# 9_-_UV_OV_Protection.net
KiCad netlist of a schematic drawn in Altium Designer
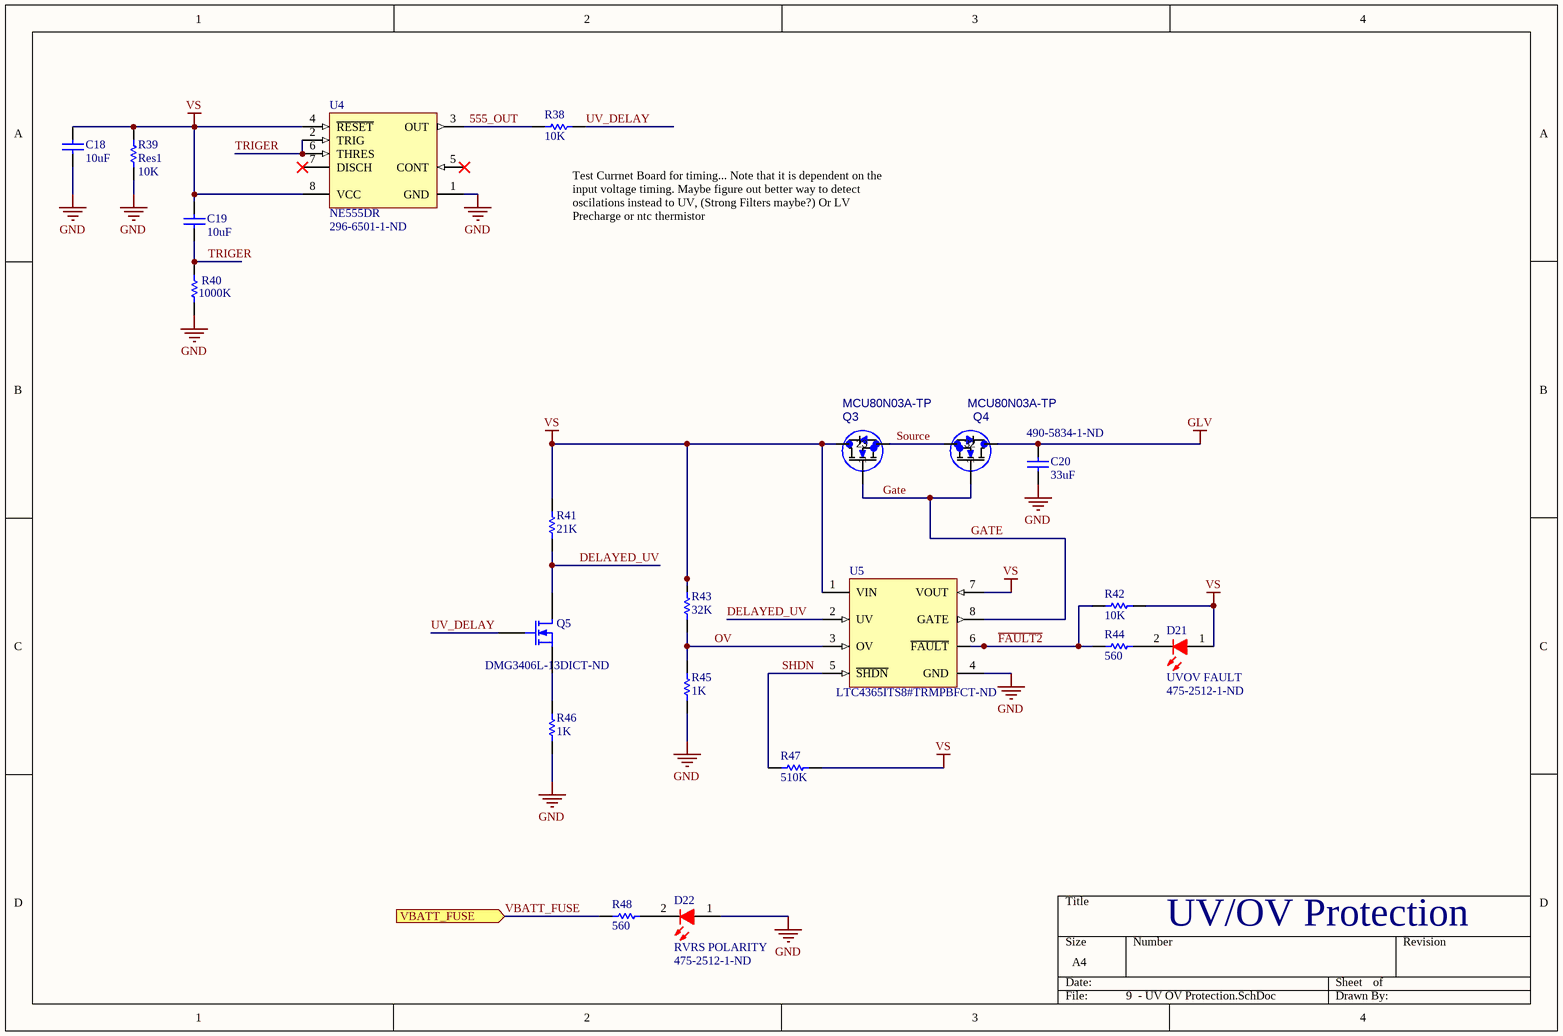
[diagram p0: 9  - UV OV Protection.SchDoc]

(export (version "E")
  (design (tool "Eeschema 10.0.6"))
  (components
    (comp (ref "C18")
      (value "10uF")
      (footprint "1608[0603]")
      (description "Capacitor (Semiconductor SIM Model)")
      (fields (field (name "Comment") "Cap Semi") (field (name "PUBLISHER") "Altium Limited"))
      (libsource (lib "Miscellaneous Devices") (part "Cap Semi"))
    )
    (comp (ref "C19")
      (value "10uF")
      (footprint "1608[0603]")
      (description "Capacitor (Semiconductor SIM Model)")
      (fields (field (name "Comment") "Cap Semi") (field (name "PUBLISHER") "Altium Limited"))
      (libsource (lib "Miscellaneous Devices") (part "Cap Semi"))
    )
    (comp (ref "C20")
      (value "33uF")
      (footprint "2J-Lead 6.1 x 5.3")
      (description "Capacitor (Semiconductor SIM Model)")
      (fields
        (field (name "SUPPLIER PART NUMBER 1") "490-5834-1-ND")
        (field (name "Comment") "Cap Semi")
        (field (name "PUBLISHER") "Altium Limited")
      )
      (libsource (lib "Miscellaneous Devices") (part "Cap Semi"))
    )
    (comp (ref "D21")
      (value "UVOV FAULT")
      (footprint "TOSH-0603LED_RED_V")
      (description "LED, Red 0603 (1608) 63mCd")
      (fields
        (field (name "MANUFACTURER") "Toshiba")
        (field (name "PARTNUMBER") "TLSU1008A(T04)")
        (field (name "SUPPLIER PART NUMBER 1") "475-2512-1-ND")
      )
      (libsource (lib "Altium Content Vault") (part "CMP-0444-00001-1"))
    )
    (comp (ref "D22")
      (value "RVRS POLARITY")
      (footprint "TOSH-0603LED_RED_V")
      (description "LED, Red 0603 (1608) 63mCd")
      (fields
        (field (name "MANUFACTURER") "Toshiba")
        (field (name "PARTNUMBER") "TLSU1008A(T04)")
        (field (name "SUPPLIER PART NUMBER 1") "475-2512-1-ND")
      )
      (libsource (lib "Altium Content Vault") (part "CMP-0444-00001-1"))
    )
    (comp (ref "Q3")
      (value "MCU80N03A-TP")
      (footprint "MCU80N_MCE")
      (fields (field (name "COPYRIGHT") "Copyright (C) 2022 Ultra Librarian. All rights reserved."))
      (libsource (lib "ACB_lib") (part "MCU80N03A-TP"))
    )
    (comp (ref "Q4")
      (value "MCU80N03A-TP")
      (footprint "MCU80N_MCE")
      (fields (field (name "COPYRIGHT") "Copyright (C) 2022 Ultra Librarian. All rights reserved."))
      (libsource (lib "ACB_lib") (part "MCU80N03A-TP"))
    )
    (comp (ref "Q5")
      (value "~")
      (footprint "SOT-23_N")
      (description "N-Channel MOSFET")
      (fields
        (field (name "MANUFACTURER") "Infineon Technologies")
        (field (name "MANUFACTURER PART NUMBER") "IPD075N03L G")
        (field (name "SUPPLIER PART NUMBER 1") "DMG3406L-13DICT-ND")
        (field (name "PUBLISHER") "Altium Limited")
      )
      (libsource (lib "Miscellaneous Devices") (part "MOSFET-N"))
    )
    (comp (ref "R38")
      (value "10K")
      (footprint "RESC0603(1608)_L")
      (description "0603 (1608 Metric) Chip Resistor")
      (libsource (lib "Altium Content Vault") (part "RES_3"))
    )
    (comp (ref "R39")
      (value "Res1")
      (footprint "1608[0603]")
      (description "RES SMD 10K OHM 5% 1/4W 0603")
      (fields
        (field (name "ALTIUM_VALUE") "10K")
        (field (name "MANUFACTURER") "Rohm Semiconductor")
        (field (name "MANUFACTURER PART NUMBER") "ESR03EZPJ103")
        (field (name "PUBLISHER") "Altium Limited")
      )
      (libsource (lib "Miscellaneous Devices") (part "Res1"))
    )
    (comp (ref "R40")
      (value "1000K")
      (footprint "RESC0603(1608)_L")
      (description "0603 (1608 Metric) Chip Resistor")
      (libsource (lib "Altium Content Vault") (part "RES_3"))
    )
    (comp (ref "R41")
      (value "21K")
      (footprint "RESC0603(1608)_L")
      (description "0603 (1608 Metric) Chip Resistor")
      (libsource (lib "Altium Content Vault") (part "RES_3"))
    )
    (comp (ref "R42")
      (value "10K")
      (footprint "RESC0603(1608)_L")
      (description "0603 (1608 Metric) Chip Resistor")
      (libsource (lib "Altium Content Vault") (part "RES_3"))
    )
    (comp (ref "R43")
      (value "32K")
      (footprint "RESC0603(1608)_L")
      (description "0603 (1608 Metric) Chip Resistor")
      (libsource (lib "Altium Content Vault") (part "RES_3"))
    )
    (comp (ref "R44")
      (value "560")
      (footprint "RESC0603(1608)_L")
      (description "0603 (1608 Metric) Chip Resistor")
      (libsource (lib "Altium Content Vault") (part "RES_3"))
    )
    (comp (ref "R45")
      (value "1K")
      (footprint "RESC0603(1608)_L")
      (description "0603 (1608 Metric) Chip Resistor")
      (libsource (lib "Altium Content Vault") (part "RES_3"))
    )
    (comp (ref "R46")
      (value "1K")
      (footprint "RESC0603(1608)_L")
      (description "0603 (1608 Metric) Chip Resistor")
      (libsource (lib "Altium Content Vault") (part "RES_3"))
    )
    (comp (ref "R47")
      (value "510K")
      (footprint "RESC0603(1608)_L")
      (description "0603 (1608 Metric) Chip Resistor")
      (libsource (lib "Altium Content Vault") (part "RES_3"))
    )
    (comp (ref "R48")
      (value "560")
      (footprint "RESC0603(1608)_L")
      (description "0603 (1608 Metric) Chip Resistor")
      (libsource (lib "Altium Content Vault") (part "RES_3"))
    )
    (comp (ref "U4")
      (value "NE555DR")
      (footprint "D0008A_M")
      (fields (field (name "SUPPLIER PART NUMBER 1") "296-6501-1-ND"))
      (libsource (lib "Altium Content Vault") (part "CMP-1685-00007-1"))
    )
    (comp (ref "U5")
      (value "LTC4365ITS8#TRMPBF")
      (footprint "LT-TS8-8-TSOT-23_V")
      (fields
        (field (name "MANUFACTURER") "Linear Technology")
        (field (name "SUPPLIER PART NUMBER 1") "LTC4365ITS8#TRMPBFCT-ND")
      )
      (libsource (lib "Altium Content Vault") (part "LT-LTC4365-TS8-8"))
    )
  )
  (nets
    (net (code "1") (name "/555_OUT") (class "Default")
      (node (ref "R38") (pin "1") (pinfunction "1_1") (pintype "passive"))
      (node (ref "U4") (pin "3") (pinfunction "OUT_3") (pintype "output"))
    )
    (net (code "2") (name "/DELAYED_UV") (class "Default")
      (node (ref "Q5") (pin "3") (pinfunction "D_3") (pintype "passive"))
      (node (ref "R41") (pin "2") (pinfunction "2_2") (pintype "passive"))
      (node (ref "U5") (pin "2") (pinfunction "UV_2") (pintype "input"))
    )
    (net (code "3") (name "/GATE") (class "Default")
      (node (ref "Q3") (pin "1") (pinfunction "1_1") (pintype "passive"))
      (node (ref "Q4") (pin "1") (pinfunction "1_1") (pintype "passive"))
      (node (ref "U5") (pin "8") (pinfunction "GATE_8") (pintype "output"))
    )
    (net (code "4") (name "/OV") (class "Default")
      (node (ref "R43") (pin "1") (pinfunction "1_1") (pintype "passive"))
      (node (ref "R45") (pin "2") (pinfunction "2_2") (pintype "passive"))
      (node (ref "U5") (pin "3") (pinfunction "OV_3") (pintype "input"))
    )
    (net (code "5") (name "/SHDN") (class "Default")
      (node (ref "R47") (pin "2") (pinfunction "2_2") (pintype "passive"))
      (node (ref "U5") (pin "5") (pinfunction "~{SHDN}_5") (pintype "input"))
    )
    (net (code "6") (name "/Source") (class "Default")
      (node (ref "Q3") (pin "3") (pinfunction "3_3") (pintype "passive"))
      (node (ref "Q4") (pin "3") (pinfunction "3_3") (pintype "passive"))
    )
    (net (code "7") (name "/TRIGER") (class "Default")
      (node (ref "C19") (pin "1") (pinfunction "1_1") (pintype "passive"))
      (node (ref "R40") (pin "2") (pinfunction "2_2") (pintype "passive"))
      (node (ref "U4") (pin "2") (pinfunction "TRIG_2") (pintype "input"))
      (node (ref "U4") (pin "6") (pinfunction "THRES_6") (pintype "input"))
    )
    (net (code "8") (name "/UV_DELAY") (class "Default")
      (node (ref "Q5") (pin "1") (pinfunction "G_1") (pintype "passive"))
      (node (ref "R38") (pin "2") (pinfunction "2_2") (pintype "passive"))
    )
    (net (code "9") (name "/VBATT_FUSE") (class "Default")
      (node (ref "R48") (pin "1") (pinfunction "1_1") (pintype "passive"))
    )
    (net (code "10") (name "/~{FAULT2}") (class "Default")
      (node (ref "R42") (pin "2") (pinfunction "2_2") (pintype "passive"))
      (node (ref "R44") (pin "1") (pinfunction "1_1") (pintype "passive"))
      (node (ref "U5") (pin "6") (pinfunction "~{FAULT}_6") (pintype "open_collector"))
    )
    (net (code "11") (name "GLV") (class "Default")
      (node (ref "C20") (pin "1") (pinfunction "1_1") (pintype "passive"))
      (node (ref "Q4") (pin "2") (pinfunction "2_2") (pintype "passive"))
    )
    (net (code "12") (name "GND") (class "Default")
      (node (ref "C18") (pin "1") (pinfunction "1_1") (pintype "passive"))
      (node (ref "C20") (pin "2") (pinfunction "2_2") (pintype "passive"))
      (node (ref "D22") (pin "1") (pinfunction "A_1") (pintype "passive"))
      (node (ref "R39") (pin "1") (pinfunction "1_1") (pintype "passive"))
      (node (ref "R40") (pin "1") (pinfunction "1_1") (pintype "passive"))
      (node (ref "R45") (pin "1") (pinfunction "1_1") (pintype "passive"))
      (node (ref "R46") (pin "2") (pinfunction "2_2") (pintype "passive"))
      (node (ref "U4") (pin "1") (pinfunction "GND_1") (pintype "power_in"))
      (node (ref "U5") (pin "4") (pinfunction "GND_4") (pintype "power_in"))
    )
    (net (code "13") (name "Net-(D21-K)") (class "Default")
      (node (ref "D21") (pin "2") (pinfunction "K_2") (pintype "passive"))
      (node (ref "R44") (pin "2") (pinfunction "2_2") (pintype "passive"))
    )
    (net (code "14") (name "Net-(D22-K)") (class "Default")
      (node (ref "D22") (pin "2") (pinfunction "K_2") (pintype "passive"))
      (node (ref "R48") (pin "2") (pinfunction "2_2") (pintype "passive"))
    )
    (net (code "15") (name "Net-(Q5-S)") (class "Default")
      (node (ref "Q5") (pin "2") (pinfunction "S_2") (pintype "passive"))
      (node (ref "R46") (pin "1") (pinfunction "1_1") (pintype "passive"))
    )
    (net (code "16") (name "VS") (class "Default")
      (node (ref "C18") (pin "2") (pinfunction "2_2") (pintype "passive"))
      (node (ref "C19") (pin "2") (pinfunction "2_2") (pintype "passive"))
      (node (ref "D21") (pin "1") (pinfunction "A_1") (pintype "passive"))
      (node (ref "Q3") (pin "2") (pinfunction "2_2") (pintype "passive"))
      (node (ref "R39") (pin "2") (pinfunction "2_2") (pintype "passive"))
      (node (ref "R41") (pin "1") (pinfunction "1_1") (pintype "passive"))
      (node (ref "R42") (pin "1") (pinfunction "1_1") (pintype "passive"))
      (node (ref "R43") (pin "2") (pinfunction "2_2") (pintype "passive"))
      (node (ref "R47") (pin "1") (pinfunction "1_1") (pintype "passive"))
      (node (ref "U4") (pin "4") (pinfunction "~{RESET}_4") (pintype "input"))
      (node (ref "U4") (pin "8") (pinfunction "VCC_8") (pintype "power_in"))
      (node (ref "U5") (pin "1") (pinfunction "VIN_1") (pintype "power_in"))
      (node (ref "U5") (pin "7") (pinfunction "VOUT_7") (pintype "input"))
    )
    (net (code "17") (name "unconnected-(U4-CONT-Pad5)") (class "Default")
      (node (ref "U4") (pin "5") (pinfunction "CONT_5") (pintype "input+no_connect"))
    )
    (net (code "18") (name "unconnected-(U4-DISCH-Pad7)") (class "Default")
      (node (ref "U4") (pin "7") (pinfunction "DISCH_7") (pintype "open_collector+no_connect"))
    )
  )
)
